# mimic1567.net
KiCad netlist of a schematic drawn in EAGLE
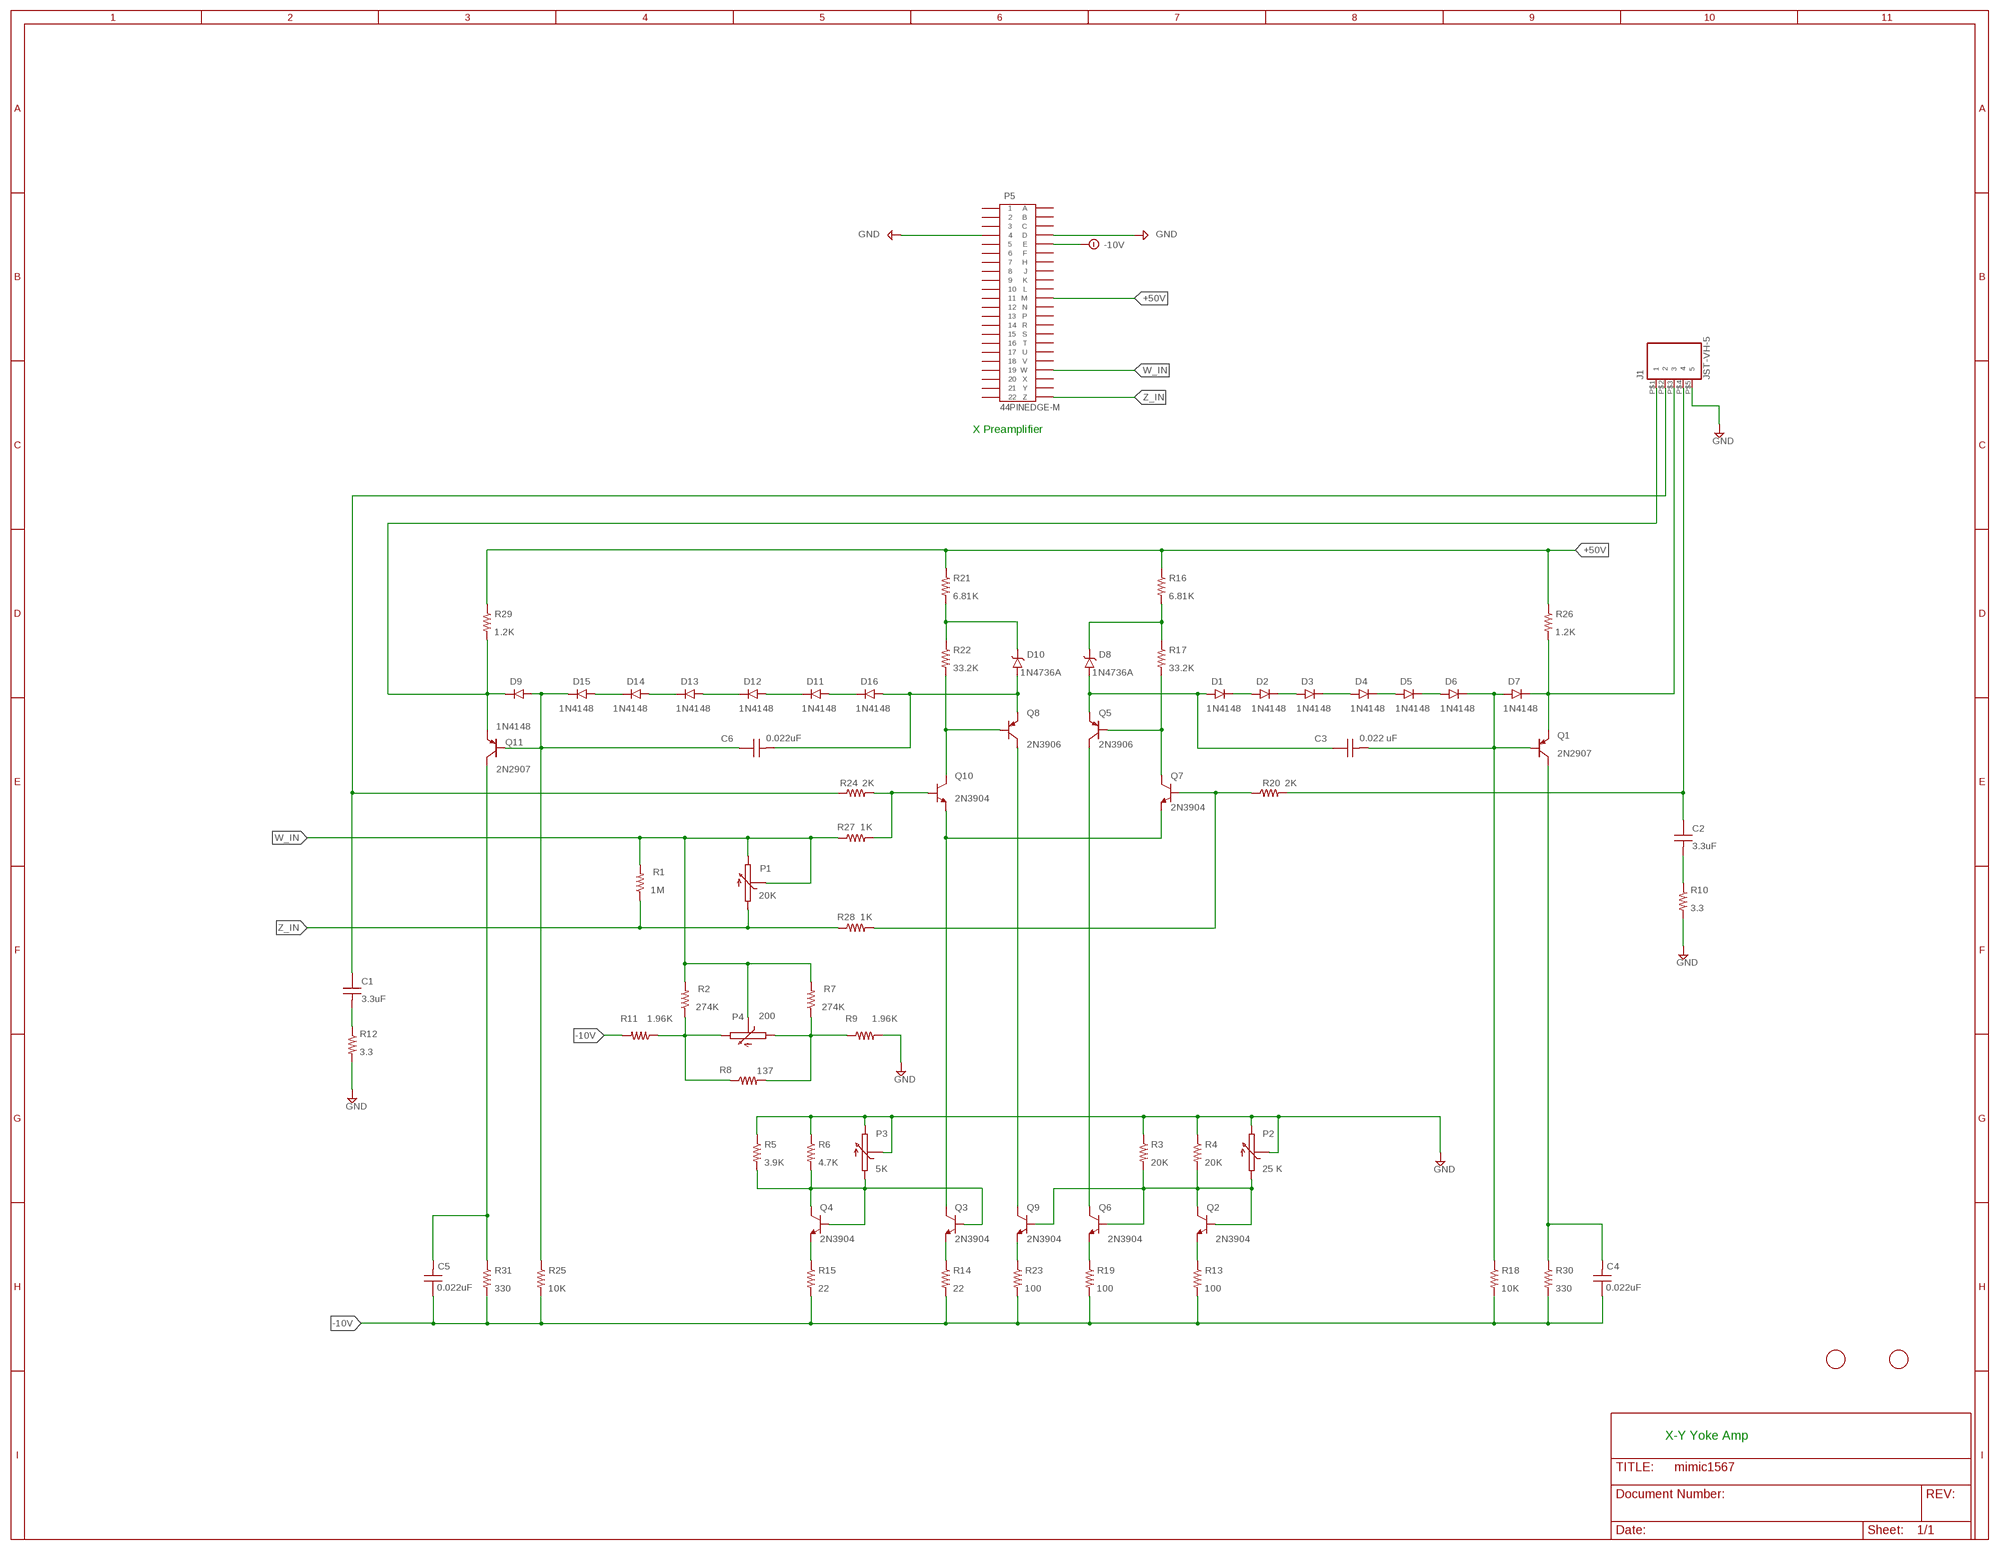
[diagram p0: schematic, sheet 1]

(export (version "E")
  (design (tool "Eeschema 10.0.6"))
  (components
    (comp (ref "C1")
      (value "3.3uF")
      (footprint "eagle-import:CAP-3-PT-ZERO-3UF-250V-FILM")
      (libsource (lib "eagle-import") (part "ECQ-E2335JF"))
    )
    (comp (ref "C2")
      (value "3.3uF")
      (footprint "eagle-import:CAP-3-PT-ZERO-3UF-250V-FILM")
      (libsource (lib "eagle-import") (part "ECQ-E2335JF"))
    )
    (comp (ref "C3")
      (value "0.022 uF")
      (footprint "eagle-import:CAP-ZERO-PT-ZERO-22UF-250V-FILM")
      (libsource (lib "eagle-import") (part "ECQ-E2223JF"))
    )
    (comp (ref "C4")
      (value "0.022uF")
      (footprint "eagle-import:CAP-ZERO-PT-ZERO-22UF-250V-FILM")
      (libsource (lib "eagle-import") (part "ECQ-E2223JF"))
    )
    (comp (ref "C5")
      (value "0.022uF")
      (footprint "eagle-import:CAP-ZERO-PT-ZERO-22UF-250V-FILM")
      (libsource (lib "eagle-import") (part "ECQ-E2223JF"))
    )
    (comp (ref "C6")
      (value "0.022uF")
      (footprint "eagle-import:CAP-ZERO-PT-ZERO-22UF-250V-FILM")
      (libsource (lib "eagle-import") (part "ECQ-E2223JF"))
    )
    (comp (ref "D1")
      (value "1N4148")
      (footprint "eagle-import:DO35-7")
      (libsource (lib "eagle-import") (part "1N4148"))
    )
    (comp (ref "D2")
      (value "1N4148")
      (footprint "eagle-import:DO35-7")
      (libsource (lib "eagle-import") (part "1N4148"))
    )
    (comp (ref "D3")
      (value "1N4148")
      (footprint "eagle-import:DO35-7")
      (libsource (lib "eagle-import") (part "1N4148"))
    )
    (comp (ref "D4")
      (value "1N4148")
      (footprint "eagle-import:DO35-7")
      (libsource (lib "eagle-import") (part "1N4148"))
    )
    (comp (ref "D5")
      (value "1N4148")
      (footprint "eagle-import:DO35-7")
      (libsource (lib "eagle-import") (part "1N4148"))
    )
    (comp (ref "D6")
      (value "1N4148")
      (footprint "eagle-import:DO35-7")
      (libsource (lib "eagle-import") (part "1N4148"))
    )
    (comp (ref "D7")
      (value "1N4148")
      (footprint "eagle-import:DO35-7")
      (libsource (lib "eagle-import") (part "1N4148"))
    )
    (comp (ref "D8")
      (value "1N4736A")
      (footprint "eagle-import:DO41")
      (libsource (lib "eagle-import") (part "1N4736A"))
    )
    (comp (ref "D9")
      (value "1N4148")
      (footprint "eagle-import:DO35-7")
      (libsource (lib "eagle-import") (part "1N4148"))
    )
    (comp (ref "D10")
      (value "1N4736A")
      (footprint "eagle-import:DO41")
      (libsource (lib "eagle-import") (part "1N4736A"))
    )
    (comp (ref "D11")
      (value "1N4148")
      (footprint "eagle-import:DO35-7")
      (libsource (lib "eagle-import") (part "1N4148"))
    )
    (comp (ref "D12")
      (value "1N4148")
      (footprint "eagle-import:DO35-7")
      (libsource (lib "eagle-import") (part "1N4148"))
    )
    (comp (ref "D13")
      (value "1N4148")
      (footprint "eagle-import:DO35-7")
      (libsource (lib "eagle-import") (part "1N4148"))
    )
    (comp (ref "D14")
      (value "1N4148")
      (footprint "eagle-import:DO35-7")
      (libsource (lib "eagle-import") (part "1N4148"))
    )
    (comp (ref "D15")
      (value "1N4148")
      (footprint "eagle-import:DO35-7")
      (libsource (lib "eagle-import") (part "1N4148"))
    )
    (comp (ref "D16")
      (value "1N4148")
      (footprint "eagle-import:DO35-7")
      (libsource (lib "eagle-import") (part "1N4148"))
    )
    (comp (ref "J1")
      (value "JST-VH-5")
      (footprint "eagle-import:VHR-5N")
      (libsource (lib "eagle-import") (part "JST-VH-5"))
    )
    (comp (ref "P1")
      (value "20K")
      (footprint "eagle-import:3006P")
      (libsource (lib "eagle-import") (part "POT-3006P"))
    )
    (comp (ref "P2")
      (value "25 K")
      (footprint "eagle-import:3006P")
      (libsource (lib "eagle-import") (part "POT-3006P"))
    )
    (comp (ref "P3")
      (value "5K")
      (footprint "eagle-import:3006P")
      (libsource (lib "eagle-import") (part "POT-3006P"))
    )
    (comp (ref "P4")
      (value "200")
      (footprint "eagle-import:3006P")
      (libsource (lib "eagle-import") (part "POT-3006P"))
    )
    (comp (ref "P5")
      (value "44PINEDGE-M")
      (footprint "eagle-import:44PINEDGE")
      (libsource (lib "eagle-import") (part "44PINEDGE-M"))
    )
    (comp (ref "Q1")
      (value "2N2907")
      (footprint "eagle-import:TO18")
      (libsource (lib "eagle-import") (part "2N2907"))
    )
    (comp (ref "Q2")
      (value "2N3904")
      (footprint "eagle-import:TO92")
      (libsource (lib "eagle-import") (part "2N3904"))
    )
    (comp (ref "Q3")
      (value "2N3904")
      (footprint "eagle-import:TO92")
      (libsource (lib "eagle-import") (part "2N3904"))
    )
    (comp (ref "Q4")
      (value "2N3904")
      (footprint "eagle-import:TO92")
      (libsource (lib "eagle-import") (part "2N3904"))
    )
    (comp (ref "Q5")
      (value "2N3906")
      (footprint "eagle-import:TO92")
      (libsource (lib "eagle-import") (part "2N3906"))
    )
    (comp (ref "Q6")
      (value "2N3904")
      (footprint "eagle-import:TO92")
      (libsource (lib "eagle-import") (part "2N3904"))
    )
    (comp (ref "Q7")
      (value "2N3904")
      (footprint "eagle-import:TO92")
      (libsource (lib "eagle-import") (part "2N3904"))
    )
    (comp (ref "Q8")
      (value "2N3906")
      (footprint "eagle-import:TO92")
      (libsource (lib "eagle-import") (part "2N3906"))
    )
    (comp (ref "Q9")
      (value "2N3904")
      (footprint "eagle-import:TO92")
      (libsource (lib "eagle-import") (part "2N3904"))
    )
    (comp (ref "Q10")
      (value "2N3904")
      (footprint "eagle-import:TO92")
      (libsource (lib "eagle-import") (part "2N3904"))
    )
    (comp (ref "Q11")
      (value "2N2907")
      (footprint "eagle-import:TO18")
      (libsource (lib "eagle-import") (part "2N2907"))
    )
    (comp (ref "R1")
      (value "1M")
      (footprint "eagle-import:R_QUARTERWATT")
      (libsource (lib "eagle-import") (part "AXIALRESISTORQUARTER_WATT"))
    )
    (comp (ref "R2")
      (value "274K")
      (footprint "eagle-import:R_QUARTERWATT")
      (libsource (lib "eagle-import") (part "AXIALRESISTORQUARTER_WATT"))
    )
    (comp (ref "R3")
      (value "20K")
      (footprint "eagle-import:R_QUARTERWATT")
      (libsource (lib "eagle-import") (part "AXIALRESISTORQUARTER_WATT"))
    )
    (comp (ref "R4")
      (value "20K")
      (footprint "eagle-import:R_QUARTERWATT")
      (libsource (lib "eagle-import") (part "AXIALRESISTORQUARTER_WATT"))
    )
    (comp (ref "R5")
      (value "3.9K")
      (footprint "eagle-import:R_QUARTERWATT")
      (libsource (lib "eagle-import") (part "AXIALRESISTORQUARTER_WATT"))
    )
    (comp (ref "R6")
      (value "4.7K")
      (footprint "eagle-import:R_QUARTERWATT")
      (libsource (lib "eagle-import") (part "AXIALRESISTORQUARTER_WATT"))
    )
    (comp (ref "R7")
      (value "274K")
      (footprint "eagle-import:R_QUARTERWATT")
      (libsource (lib "eagle-import") (part "AXIALRESISTORQUARTER_WATT"))
    )
    (comp (ref "R8")
      (value "137")
      (footprint "eagle-import:R_QUARTERWATT")
      (libsource (lib "eagle-import") (part "AXIALRESISTORQUARTER_WATT"))
    )
    (comp (ref "R9")
      (value "1.96K")
      (footprint "eagle-import:R_QUARTERWATT")
      (libsource (lib "eagle-import") (part "AXIALRESISTORQUARTER_WATT"))
    )
    (comp (ref "R10")
      (value "3.3")
      (footprint "eagle-import:0309_12")
      (libsource (lib "eagle-import") (part "R-1/2WATT"))
    )
    (comp (ref "R11")
      (value "1.96K")
      (footprint "eagle-import:R_QUARTERWATT")
      (libsource (lib "eagle-import") (part "AXIALRESISTORQUARTER_WATT"))
    )
    (comp (ref "R12")
      (value "3.3")
      (footprint "eagle-import:0309_12")
      (libsource (lib "eagle-import") (part "R-1/2WATT"))
    )
    (comp (ref "R13")
      (value "100")
      (footprint "eagle-import:R_QUARTERWATT")
      (libsource (lib "eagle-import") (part "AXIALRESISTORQUARTER_WATT"))
    )
    (comp (ref "R14")
      (value "22")
      (footprint "eagle-import:R_QUARTERWATT")
      (libsource (lib "eagle-import") (part "AXIALRESISTORQUARTER_WATT"))
    )
    (comp (ref "R15")
      (value "22")
      (footprint "eagle-import:R_QUARTERWATT")
      (libsource (lib "eagle-import") (part "AXIALRESISTORQUARTER_WATT"))
    )
    (comp (ref "R16")
      (value "6.81K")
      (footprint "eagle-import:R_HALFWATT")
      (libsource (lib "eagle-import") (part "AXIALRESISTORHALF_WATT"))
    )
    (comp (ref "R17")
      (value "33.2K")
      (footprint "eagle-import:R_HALFWATT")
      (libsource (lib "eagle-import") (part "AXIALRESISTORHALF_WATT"))
    )
    (comp (ref "R18")
      (value "10K")
      (footprint "eagle-import:R_HALFWATT")
      (libsource (lib "eagle-import") (part "AXIALRESISTORHALF_WATT"))
    )
    (comp (ref "R19")
      (value "100")
      (footprint "eagle-import:R_QUARTERWATT")
      (libsource (lib "eagle-import") (part "AXIALRESISTORQUARTER_WATT"))
    )
    (comp (ref "R20")
      (value "2K")
      (footprint "eagle-import:R_QUARTERWATT")
      (libsource (lib "eagle-import") (part "AXIALRESISTORQUARTER_WATT"))
    )
    (comp (ref "R21")
      (value "6.81K")
      (footprint "eagle-import:R_HALFWATT")
      (libsource (lib "eagle-import") (part "AXIALRESISTORHALF_WATT"))
    )
    (comp (ref "R22")
      (value "33.2K")
      (footprint "eagle-import:R_HALFWATT")
      (libsource (lib "eagle-import") (part "AXIALRESISTORHALF_WATT"))
    )
    (comp (ref "R23")
      (value "100")
      (footprint "eagle-import:R_QUARTERWATT")
      (libsource (lib "eagle-import") (part "AXIALRESISTORQUARTER_WATT"))
    )
    (comp (ref "R24")
      (value "2K")
      (footprint "eagle-import:R_QUARTERWATT")
      (libsource (lib "eagle-import") (part "AXIALRESISTORQUARTER_WATT"))
    )
    (comp (ref "R25")
      (value "10K")
      (footprint "eagle-import:R_HALFWATT")
      (libsource (lib "eagle-import") (part "AXIALRESISTORHALF_WATT"))
    )
    (comp (ref "R26")
      (value "1.2K")
      (footprint "eagle-import:R_FIVEWATT")
      (libsource (lib "eagle-import") (part "R-5WATT"))
    )
    (comp (ref "R27")
      (value "1K")
      (footprint "eagle-import:R_QUARTERWATT")
      (libsource (lib "eagle-import") (part "AXIALRESISTORQUARTER_WATT"))
    )
    (comp (ref "R28")
      (value "1K")
      (footprint "eagle-import:R_QUARTERWATT")
      (libsource (lib "eagle-import") (part "AXIALRESISTORQUARTER_WATT"))
    )
    (comp (ref "R29")
      (value "1.2K")
      (footprint "eagle-import:R_FIVEWATT")
      (libsource (lib "eagle-import") (part "R-5WATT"))
    )
    (comp (ref "R30")
      (value "330")
      (footprint "eagle-import:R_ONEWATT")
      (libsource (lib "eagle-import") (part "AXIALRESISTORONE_WATT"))
    )
    (comp (ref "R31")
      (value "330")
      (footprint "eagle-import:R_ONEWATT")
      (libsource (lib "eagle-import") (part "AXIALRESISTORONE_WATT"))
    )
    (comp (ref "U$1")
      (value "FIDUCIAL")
      (footprint "eagle-import:FIDUCIAL_1MM")
      (libsource (lib "eagle-import") (part "FIDUCIAL"))
    )
    (comp (ref "U$2")
      (value "FIDUCIAL")
      (footprint "eagle-import:FIDUCIAL_1MM")
      (libsource (lib "eagle-import") (part "FIDUCIAL"))
    )
  )
  (nets
    (net (code "1") (name "+50V") (class "Default")
      (node (ref "P5") (pin "M") (pinfunction "M_M") (pintype "passive"))
      (node (ref "R16") (pin "1") (pinfunction "P$1_1") (pintype "passive"))
      (node (ref "R21") (pin "1") (pinfunction "P$1_1") (pintype "passive"))
      (node (ref "R26") (pin "1") (pinfunction "P$1_1") (pintype "passive"))
      (node (ref "R29") (pin "1") (pinfunction "P$1_1") (pintype "passive"))
    )
    (net (code "2") (name "-10V") (class "Default")
      (node (ref "C4") (pin "1") (pinfunction "1_1") (pintype "passive"))
      (node (ref "C5") (pin "1") (pinfunction "1_1") (pintype "passive"))
      (node (ref "P5") (pin "E") (pinfunction "E_E") (pintype "passive"))
      (node (ref "R11") (pin "2") (pinfunction "P$2_2") (pintype "passive"))
      (node (ref "R13") (pin "2") (pinfunction "P$2_2") (pintype "passive"))
      (node (ref "R14") (pin "2") (pinfunction "P$2_2") (pintype "passive"))
      (node (ref "R15") (pin "2") (pinfunction "P$2_2") (pintype "passive"))
      (node (ref "R18") (pin "2") (pinfunction "P$2_2") (pintype "passive"))
      (node (ref "R19") (pin "2") (pinfunction "P$2_2") (pintype "passive"))
      (node (ref "R23") (pin "2") (pinfunction "P$2_2") (pintype "passive"))
      (node (ref "R25") (pin "2") (pinfunction "P$2_2") (pintype "passive"))
      (node (ref "R30") (pin "2") (pinfunction "P$2_2") (pintype "passive"))
      (node (ref "R31") (pin "2") (pinfunction "P$2_2") (pintype "passive"))
    )
    (net (code "3") (name "GND") (class "Default")
      (node (ref "J1") (pin "P$5") (pinfunction "5_P$5") (pintype "bidirectional"))
      (node (ref "P2") (pin "2") (pinfunction "2_2") (pintype "passive"))
      (node (ref "P2") (pin "3") (pinfunction "3_3") (pintype "passive"))
      (node (ref "P3") (pin "2") (pinfunction "2_2") (pintype "passive"))
      (node (ref "P3") (pin "3") (pinfunction "3_3") (pintype "passive"))
      (node (ref "P5") (pin "4") (pinfunction "4_4") (pintype "passive"))
      (node (ref "P5") (pin "D") (pinfunction "D_D") (pintype "passive"))
      (node (ref "R10") (pin "2") (pinfunction "P$2_2") (pintype "passive"))
      (node (ref "R12") (pin "2") (pinfunction "P$2_2") (pintype "passive"))
      (node (ref "R3") (pin "1") (pinfunction "P$1_1") (pintype "passive"))
      (node (ref "R4") (pin "1") (pinfunction "P$1_1") (pintype "passive"))
      (node (ref "R5") (pin "1") (pinfunction "P$1_1") (pintype "passive"))
      (node (ref "R6") (pin "1") (pinfunction "P$1_1") (pintype "passive"))
      (node (ref "R9") (pin "2") (pinfunction "P$2_2") (pintype "passive"))
    )
    (net (code "4") (name "Net-(D1-PadC)") (class "Default")
      (node (ref "D1") (pin "C") (pinfunction "C_C") (pintype "passive"))
      (node (ref "D2") (pin "A") (pinfunction "A_A") (pintype "passive"))
    )
    (net (code "5") (name "Net-(D2-PadC)") (class "Default")
      (node (ref "D2") (pin "C") (pinfunction "C_C") (pintype "passive"))
      (node (ref "D3") (pin "A") (pinfunction "A_A") (pintype "passive"))
    )
    (net (code "6") (name "Net-(D3-PadC)") (class "Default")
      (node (ref "D3") (pin "C") (pinfunction "C_C") (pintype "passive"))
      (node (ref "D4") (pin "A") (pinfunction "A_A") (pintype "passive"))
    )
    (net (code "7") (name "Net-(D4-PadC)") (class "Default")
      (node (ref "D4") (pin "C") (pinfunction "C_C") (pintype "passive"))
      (node (ref "D5") (pin "A") (pinfunction "A_A") (pintype "passive"))
    )
    (net (code "8") (name "Net-(D5-PadC)") (class "Default")
      (node (ref "D5") (pin "C") (pinfunction "C_C") (pintype "passive"))
      (node (ref "D6") (pin "A") (pinfunction "A_A") (pintype "passive"))
    )
    (net (code "9") (name "Net-(D11-PadA)") (class "Default")
      (node (ref "D11") (pin "A") (pinfunction "A_A") (pintype "passive"))
      (node (ref "D16") (pin "C") (pinfunction "C_C") (pintype "passive"))
    )
    (net (code "10") (name "Net-(D11-PadC)") (class "Default")
      (node (ref "D11") (pin "C") (pinfunction "C_C") (pintype "passive"))
      (node (ref "D12") (pin "A") (pinfunction "A_A") (pintype "passive"))
    )
    (net (code "11") (name "Net-(D12-PadC)") (class "Default")
      (node (ref "D12") (pin "C") (pinfunction "C_C") (pintype "passive"))
      (node (ref "D13") (pin "A") (pinfunction "A_A") (pintype "passive"))
    )
    (net (code "12") (name "Net-(D13-PadC)") (class "Default")
      (node (ref "D13") (pin "C") (pinfunction "C_C") (pintype "passive"))
      (node (ref "D14") (pin "A") (pinfunction "A_A") (pintype "passive"))
    )
    (net (code "13") (name "Net-(D14-PadC)") (class "Default")
      (node (ref "D14") (pin "C") (pinfunction "C_C") (pintype "passive"))
      (node (ref "D15") (pin "A") (pinfunction "A_A") (pintype "passive"))
    )
    (net (code "14") (name "Net-(J1-1)") (class "Default")
      (node (ref "D9") (pin "C") (pinfunction "C_C") (pintype "passive"))
      (node (ref "J1") (pin "P$1") (pinfunction "1_P$1") (pintype "bidirectional"))
      (node (ref "Q11") (pin "1") (pinfunction "E_1") (pintype "passive"))
      (node (ref "R29") (pin "2") (pinfunction "P$2_2") (pintype "passive"))
    )
    (net (code "15") (name "Net-(J1-2)") (class "Default")
      (node (ref "C1") (pin "1") (pinfunction "1_1") (pintype "passive"))
      (node (ref "J1") (pin "P$2") (pinfunction "2_P$2") (pintype "bidirectional"))
      (node (ref "R24") (pin "1") (pinfunction "P$1_1") (pintype "passive"))
    )
    (net (code "16") (name "Net-(J1-3)") (class "Default")
      (node (ref "D7") (pin "C") (pinfunction "C_C") (pintype "passive"))
      (node (ref "J1") (pin "P$3") (pinfunction "3_P$3") (pintype "bidirectional"))
      (node (ref "Q1") (pin "1") (pinfunction "E_1") (pintype "passive"))
      (node (ref "R26") (pin "2") (pinfunction "P$2_2") (pintype "passive"))
    )
    (net (code "17") (name "Net-(J1-4)") (class "Default")
      (node (ref "C2") (pin "1") (pinfunction "1_1") (pintype "passive"))
      (node (ref "J1") (pin "P$4") (pinfunction "4_P$4") (pintype "bidirectional"))
      (node (ref "R20") (pin "2") (pinfunction "P$2_2") (pintype "passive"))
    )
    (net (code "18") (name "Net-(Q1-B)") (class "Default")
      (node (ref "C3") (pin "2") (pinfunction "2_2") (pintype "passive"))
      (node (ref "D6") (pin "C") (pinfunction "C_C") (pintype "passive"))
      (node (ref "D7") (pin "A") (pinfunction "A_A") (pintype "passive"))
      (node (ref "Q1") (pin "2") (pinfunction "B_2") (pintype "passive"))
      (node (ref "R18") (pin "1") (pinfunction "P$1_1") (pintype "passive"))
    )
    (net (code "19") (name "Net-(Q1-C)") (class "Default")
      (node (ref "C4") (pin "2") (pinfunction "2_2") (pintype "passive"))
      (node (ref "Q1") (pin "3") (pinfunction "C_3") (pintype "passive"))
      (node (ref "R30") (pin "1") (pinfunction "P$1_1") (pintype "passive"))
    )
    (net (code "20") (name "Net-(Q2-B)") (class "Default")
      (node (ref "P2") (pin "1") (pinfunction "1_1") (pintype "passive"))
      (node (ref "Q2") (pin "2") (pinfunction "B_2") (pintype "passive"))
      (node (ref "Q2") (pin "3") (pinfunction "C_3") (pintype "passive"))
      (node (ref "Q6") (pin "2") (pinfunction "B_2") (pintype "passive"))
      (node (ref "Q9") (pin "2") (pinfunction "B_2") (pintype "passive"))
      (node (ref "R3") (pin "2") (pinfunction "P$2_2") (pintype "passive"))
      (node (ref "R4") (pin "2") (pinfunction "P$2_2") (pintype "passive"))
    )
    (net (code "21") (name "Net-(Q2-E)") (class "Default")
      (node (ref "Q2") (pin "1") (pinfunction "E_1") (pintype "passive"))
      (node (ref "R13") (pin "1") (pinfunction "P$1_1") (pintype "passive"))
    )
    (net (code "22") (name "Net-(Q3-B)") (class "Default")
      (node (ref "P3") (pin "1") (pinfunction "1_1") (pintype "passive"))
      (node (ref "Q3") (pin "2") (pinfunction "B_2") (pintype "passive"))
      (node (ref "Q4") (pin "2") (pinfunction "B_2") (pintype "passive"))
      (node (ref "Q4") (pin "3") (pinfunction "C_3") (pintype "passive"))
      (node (ref "R5") (pin "2") (pinfunction "P$2_2") (pintype "passive"))
      (node (ref "R6") (pin "2") (pinfunction "P$2_2") (pintype "passive"))
    )
    (net (code "23") (name "Net-(Q3-E)") (class "Default")
      (node (ref "Q3") (pin "1") (pinfunction "E_1") (pintype "passive"))
      (node (ref "R14") (pin "1") (pinfunction "P$1_1") (pintype "passive"))
    )
    (net (code "24") (name "Net-(Q4-E)") (class "Default")
      (node (ref "Q4") (pin "1") (pinfunction "E_1") (pintype "passive"))
      (node (ref "R15") (pin "1") (pinfunction "P$1_1") (pintype "passive"))
    )
    (net (code "25") (name "Net-(Q5-B)") (class "Default")
      (node (ref "Q5") (pin "2") (pinfunction "B_2") (pintype "passive"))
      (node (ref "Q7") (pin "3") (pinfunction "C_3") (pintype "passive"))
      (node (ref "R17") (pin "2") (pinfunction "P$2_2") (pintype "passive"))
    )
    (net (code "26") (name "Net-(Q5-C)") (class "Default")
      (node (ref "Q5") (pin "1") (pinfunction "C_1") (pintype "passive"))
      (node (ref "Q6") (pin "3") (pinfunction "C_3") (pintype "passive"))
    )
    (net (code "27") (name "Net-(Q5-E)") (class "Default")
      (node (ref "C3") (pin "1") (pinfunction "1_1") (pintype "passive"))
      (node (ref "D1") (pin "A") (pinfunction "A_A") (pintype "passive"))
      (node (ref "D8") (pin "A") (pinfunction "A_A") (pintype "passive"))
      (node (ref "Q5") (pin "3") (pinfunction "E_3") (pintype "passive"))
    )
    (net (code "28") (name "Net-(Q6-E)") (class "Default")
      (node (ref "Q6") (pin "1") (pinfunction "E_1") (pintype "passive"))
      (node (ref "R19") (pin "1") (pinfunction "P$1_1") (pintype "passive"))
    )
    (net (code "29") (name "Net-(Q7-B)") (class "Default")
      (node (ref "Q7") (pin "2") (pinfunction "B_2") (pintype "passive"))
      (node (ref "R20") (pin "1") (pinfunction "P$1_1") (pintype "passive"))
      (node (ref "R28") (pin "2") (pinfunction "P$2_2") (pintype "passive"))
    )
    (net (code "30") (name "Net-(Q8-C)") (class "Default")
      (node (ref "Q8") (pin "1") (pinfunction "C_1") (pintype "passive"))
      (node (ref "Q9") (pin "3") (pinfunction "C_3") (pintype "passive"))
    )
    (net (code "31") (name "Net-(Q8-E)") (class "Default")
      (node (ref "C6") (pin "2") (pinfunction "2_2") (pintype "passive"))
      (node (ref "D10") (pin "A") (pinfunction "A_A") (pintype "passive"))
      (node (ref "D16") (pin "A") (pinfunction "A_A") (pintype "passive"))
      (node (ref "Q8") (pin "3") (pinfunction "E_3") (pintype "passive"))
    )
    (net (code "32") (name "Net-(Q9-E)") (class "Default")
      (node (ref "Q9") (pin "1") (pinfunction "E_1") (pintype "passive"))
      (node (ref "R23") (pin "1") (pinfunction "P$1_1") (pintype "passive"))
    )
    (net (code "33") (name "Net-(Q10-B)") (class "Default")
      (node (ref "Q10") (pin "2") (pinfunction "B_2") (pintype "passive"))
      (node (ref "R24") (pin "2") (pinfunction "P$2_2") (pintype "passive"))
      (node (ref "R27") (pin "2") (pinfunction "P$2_2") (pintype "passive"))
    )
    (net (code "34") (name "Net-(Q10-C)") (class "Default")
      (node (ref "Q10") (pin "3") (pinfunction "C_3") (pintype "passive"))
      (node (ref "Q8") (pin "2") (pinfunction "B_2") (pintype "passive"))
      (node (ref "R22") (pin "2") (pinfunction "P$2_2") (pintype "passive"))
    )
    (net (code "35") (name "Net-(Q10-E)") (class "Default")
      (node (ref "Q10") (pin "1") (pinfunction "E_1") (pintype "passive"))
      (node (ref "Q3") (pin "3") (pinfunction "C_3") (pintype "passive"))
      (node (ref "Q7") (pin "1") (pinfunction "E_1") (pintype "passive"))
    )
    (net (code "36") (name "Net-(Q11-B)") (class "Default")
      (node (ref "C6") (pin "1") (pinfunction "1_1") (pintype "passive"))
      (node (ref "D15") (pin "C") (pinfunction "C_C") (pintype "passive"))
      (node (ref "D9") (pin "A") (pinfunction "A_A") (pintype "passive"))
      (node (ref "Q11") (pin "2") (pinfunction "B_2") (pintype "passive"))
      (node (ref "R25") (pin "1") (pinfunction "P$1_1") (pintype "passive"))
    )
    (net (code "37") (name "Net-(Q11-C)") (class "Default")
      (node (ref "C5") (pin "2") (pinfunction "2_2") (pintype "passive"))
      (node (ref "Q11") (pin "3") (pinfunction "C_3") (pintype "passive"))
      (node (ref "R31") (pin "1") (pinfunction "P$1_1") (pintype "passive"))
    )
    (net (code "38") (name "Net-(R7-P$1)") (class "Default")
      (node (ref "P4") (pin "1") (pinfunction "1_1") (pintype "passive"))
      (node (ref "R7") (pin "1") (pinfunction "P$1_1") (pintype "passive"))
      (node (ref "R8") (pin "2") (pinfunction "P$2_2") (pintype "passive"))
      (node (ref "R9") (pin "1") (pinfunction "P$1_1") (pintype "passive"))
    )
    (net (code "39") (name "Net-(R10-P$1)") (class "Default")
      (node (ref "C2") (pin "2") (pinfunction "2_2") (pintype "passive"))
      (node (ref "R10") (pin "1") (pinfunction "P$1_1") (pintype "passive"))
    )
    (net (code "40") (name "Net-(R11-P$1)") (class "Default")
      (node (ref "P4") (pin "3") (pinfunction "3_3") (pintype "passive"))
      (node (ref "R11") (pin "1") (pinfunction "P$1_1") (pintype "passive"))
      (node (ref "R2") (pin "1") (pinfunction "P$1_1") (pintype "passive"))
      (node (ref "R8") (pin "1") (pinfunction "P$1_1") (pintype "passive"))
    )
    (net (code "41") (name "Net-(R12-P$1)") (class "Default")
      (node (ref "C1") (pin "2") (pinfunction "2_2") (pintype "passive"))
      (node (ref "R12") (pin "1") (pinfunction "P$1_1") (pintype "passive"))
    )
    (net (code "42") (name "Net-(R16-P$2)") (class "Default")
      (node (ref "D8") (pin "C") (pinfunction "C_C") (pintype "passive"))
      (node (ref "R16") (pin "2") (pinfunction "P$2_2") (pintype "passive"))
      (node (ref "R17") (pin "1") (pinfunction "P$1_1") (pintype "passive"))
    )
    (net (code "43") (name "Net-(R21-P$2)") (class "Default")
      (node (ref "D10") (pin "C") (pinfunction "C_C") (pintype "passive"))
      (node (ref "R21") (pin "2") (pinfunction "P$2_2") (pintype "passive"))
      (node (ref "R22") (pin "1") (pinfunction "P$1_1") (pintype "passive"))
    )
    (net (code "44") (name "W_IN") (class "Default")
      (node (ref "P1") (pin "2") (pinfunction "2_2") (pintype "passive"))
      (node (ref "P1") (pin "3") (pinfunction "3_3") (pintype "passive"))
      (node (ref "P4") (pin "2") (pinfunction "2_2") (pintype "passive"))
      (node (ref "P5") (pin "W") (pinfunction "W_W") (pintype "passive"))
      (node (ref "R1") (pin "2") (pinfunction "P$2_2") (pintype "passive"))
      (node (ref "R2") (pin "2") (pinfunction "P$2_2") (pintype "passive"))
      (node (ref "R27") (pin "1") (pinfunction "P$1_1") (pintype "passive"))
      (node (ref "R7") (pin "2") (pinfunction "P$2_2") (pintype "passive"))
    )
    (net (code "45") (name "Z_IN") (class "Default")
      (node (ref "P1") (pin "1") (pinfunction "1_1") (pintype "passive"))
      (node (ref "P5") (pin "Z") (pinfunction "Z_Z") (pintype "passive"))
      (node (ref "R1") (pin "1") (pinfunction "P$1_1") (pintype "passive"))
      (node (ref "R28") (pin "1") (pinfunction "P$1_1") (pintype "passive"))
    )
    (net (code "46") (name "unconnected-(P5-Pad1)") (class "Default")
      (node (ref "P5") (pin "1") (pinfunction "1_1") (pintype "passive"))
    )
    (net (code "47") (name "unconnected-(P5-Pad2)") (class "Default")
      (node (ref "P5") (pin "2") (pinfunction "2_2") (pintype "passive"))
    )
    (net (code "48") (name "unconnected-(P5-Pad3)") (class "Default")
      (node (ref "P5") (pin "3") (pinfunction "3_3") (pintype "passive"))
    )
    (net (code "49") (name "unconnected-(P5-Pad5)") (class "Default")
      (node (ref "P5") (pin "5") (pinfunction "5_5") (pintype "passive"))
    )
    (net (code "50") (name "unconnected-(P5-Pad6)") (class "Default")
      (node (ref "P5") (pin "6") (pinfunction "6_6") (pintype "passive"))
    )
    (net (code "51") (name "unconnected-(P5-Pad7)") (class "Default")
      (node (ref "P5") (pin "7") (pinfunction "7_7") (pintype "passive"))
    )
    (net (code "52") (name "unconnected-(P5-Pad8)") (class "Default")
      (node (ref "P5") (pin "8") (pinfunction "8_8") (pintype "passive"))
    )
    (net (code "53") (name "unconnected-(P5-Pad9)") (class "Default")
      (node (ref "P5") (pin "9") (pinfunction "9_9") (pintype "passive"))
    )
    (net (code "54") (name "unconnected-(P5-Pad10)") (class "Default")
      (node (ref "P5") (pin "10") (pinfunction "10_10") (pintype "passive"))
    )
    (net (code "55") (name "unconnected-(P5-Pad11)") (class "Default")
      (node (ref "P5") (pin "11") (pinfunction "11_11") (pintype "passive"))
    )
    (net (code "56") (name "unconnected-(P5-Pad12)") (class "Default")
      (node (ref "P5") (pin "12") (pinfunction "12_12") (pintype "passive"))
    )
    (net (code "57") (name "unconnected-(P5-Pad13)") (class "Default")
      (node (ref "P5") (pin "13") (pinfunction "13_13") (pintype "passive"))
    )
    (net (code "58") (name "unconnected-(P5-Pad14)") (class "Default")
      (node (ref "P5") (pin "14") (pinfunction "14_14") (pintype "passive"))
    )
    (net (code "59") (name "unconnected-(P5-Pad15)") (class "Default")
      (node (ref "P5") (pin "15") (pinfunction "15_15") (pintype "passive"))
    )
    (net (code "60") (name "unconnected-(P5-Pad16)") (class "Default")
      (node (ref "P5") (pin "16") (pinfunction "16_16") (pintype "passive"))
    )
    (net (code "61") (name "unconnected-(P5-Pad17)") (class "Default")
      (node (ref "P5") (pin "17") (pinfunction "17_17") (pintype "passive"))
    )
    (net (code "62") (name "unconnected-(P5-Pad18)") (class "Default")
      (node (ref "P5") (pin "18") (pinfunction "18_18") (pintype "passive"))
    )
    (net (code "63") (name "unconnected-(P5-Pad19)") (class "Default")
      (node (ref "P5") (pin "19") (pinfunction "19_19") (pintype "passive"))
    )
    (net (code "64") (name "unconnected-(P5-Pad20)") (class "Default")
      (node (ref "P5") (pin "20") (pinfunction "20_20") (pintype "passive"))
    )
    (net (code "65") (name "unconnected-(P5-Pad21)") (class "Default")
      (node (ref "P5") (pin "21") (pinfunction "21_21") (pintype "passive"))
    )
    (net (code "66") (name "unconnected-(P5-Pad22)") (class "Default")
      (node (ref "P5") (pin "22") (pinfunction "22_22") (pintype "passive"))
    )
    (net (code "67") (name "unconnected-(P5-PadA)") (class "Default")
      (node (ref "P5") (pin "A") (pinfunction "A_A") (pintype "passive"))
    )
    (net (code "68") (name "unconnected-(P5-PadB)") (class "Default")
      (node (ref "P5") (pin "B") (pinfunction "B_B") (pintype "passive"))
    )
    (net (code "69") (name "unconnected-(P5-PadC)") (class "Default")
      (node (ref "P5") (pin "C") (pinfunction "C_C") (pintype "passive"))
    )
    (net (code "70") (name "unconnected-(P5-PadF)") (class "Default")
      (node (ref "P5") (pin "F") (pinfunction "F_F") (pintype "passive"))
    )
    (net (code "71") (name "unconnected-(P5-PadH)") (class "Default")
      (node (ref "P5") (pin "H") (pinfunction "H_H") (pintype "passive"))
    )
    (net (code "72") (name "unconnected-(P5-PadJ)") (class "Default")
      (node (ref "P5") (pin "J") (pinfunction "J_J") (pintype "passive"))
    )
    (net (code "73") (name "unconnected-(P5-PadK)") (class "Default")
      (node (ref "P5") (pin "K") (pinfunction "K_K") (pintype "passive"))
    )
    (net (code "74") (name "unconnected-(P5-PadL)") (class "Default")
      (node (ref "P5") (pin "L") (pinfunction "L_L") (pintype "passive"))
    )
    (net (code "75") (name "unconnected-(P5-PadN)") (class "Default")
      (node (ref "P5") (pin "N") (pinfunction "N_N") (pintype "passive"))
    )
    (net (code "76") (name "unconnected-(P5-PadP)") (class "Default")
      (node (ref "P5") (pin "P") (pinfunction "P_P") (pintype "passive"))
    )
    (net (code "77") (name "unconnected-(P5-PadR)") (class "Default")
      (node (ref "P5") (pin "R") (pinfunction "R_R") (pintype "passive"))
    )
    (net (code "78") (name "unconnected-(P5-PadS)") (class "Default")
      (node (ref "P5") (pin "S") (pinfunction "S_S") (pintype "passive"))
    )
    (net (code "79") (name "unconnected-(P5-PadT)") (class "Default")
      (node (ref "P5") (pin "T") (pinfunction "T_T") (pintype "passive"))
    )
    (net (code "80") (name "unconnected-(P5-PadU)") (class "Default")
      (node (ref "P5") (pin "U") (pinfunction "U_U") (pintype "passive"))
    )
    (net (code "81") (name "unconnected-(P5-PadV)") (class "Default")
      (node (ref "P5") (pin "V") (pinfunction "V_V") (pintype "passive"))
    )
    (net (code "82") (name "unconnected-(P5-PadX)") (class "Default")
      (node (ref "P5") (pin "X") (pinfunction "X_X") (pintype "passive"))
    )
    (net (code "83") (name "unconnected-(P5-PadY)") (class "Default")
      (node (ref "P5") (pin "Y") (pinfunction "Y_Y") (pintype "passive"))
    )
  )
)
